# RCPCell.net
KiCad netlist of a schematic drawn in EAGLE
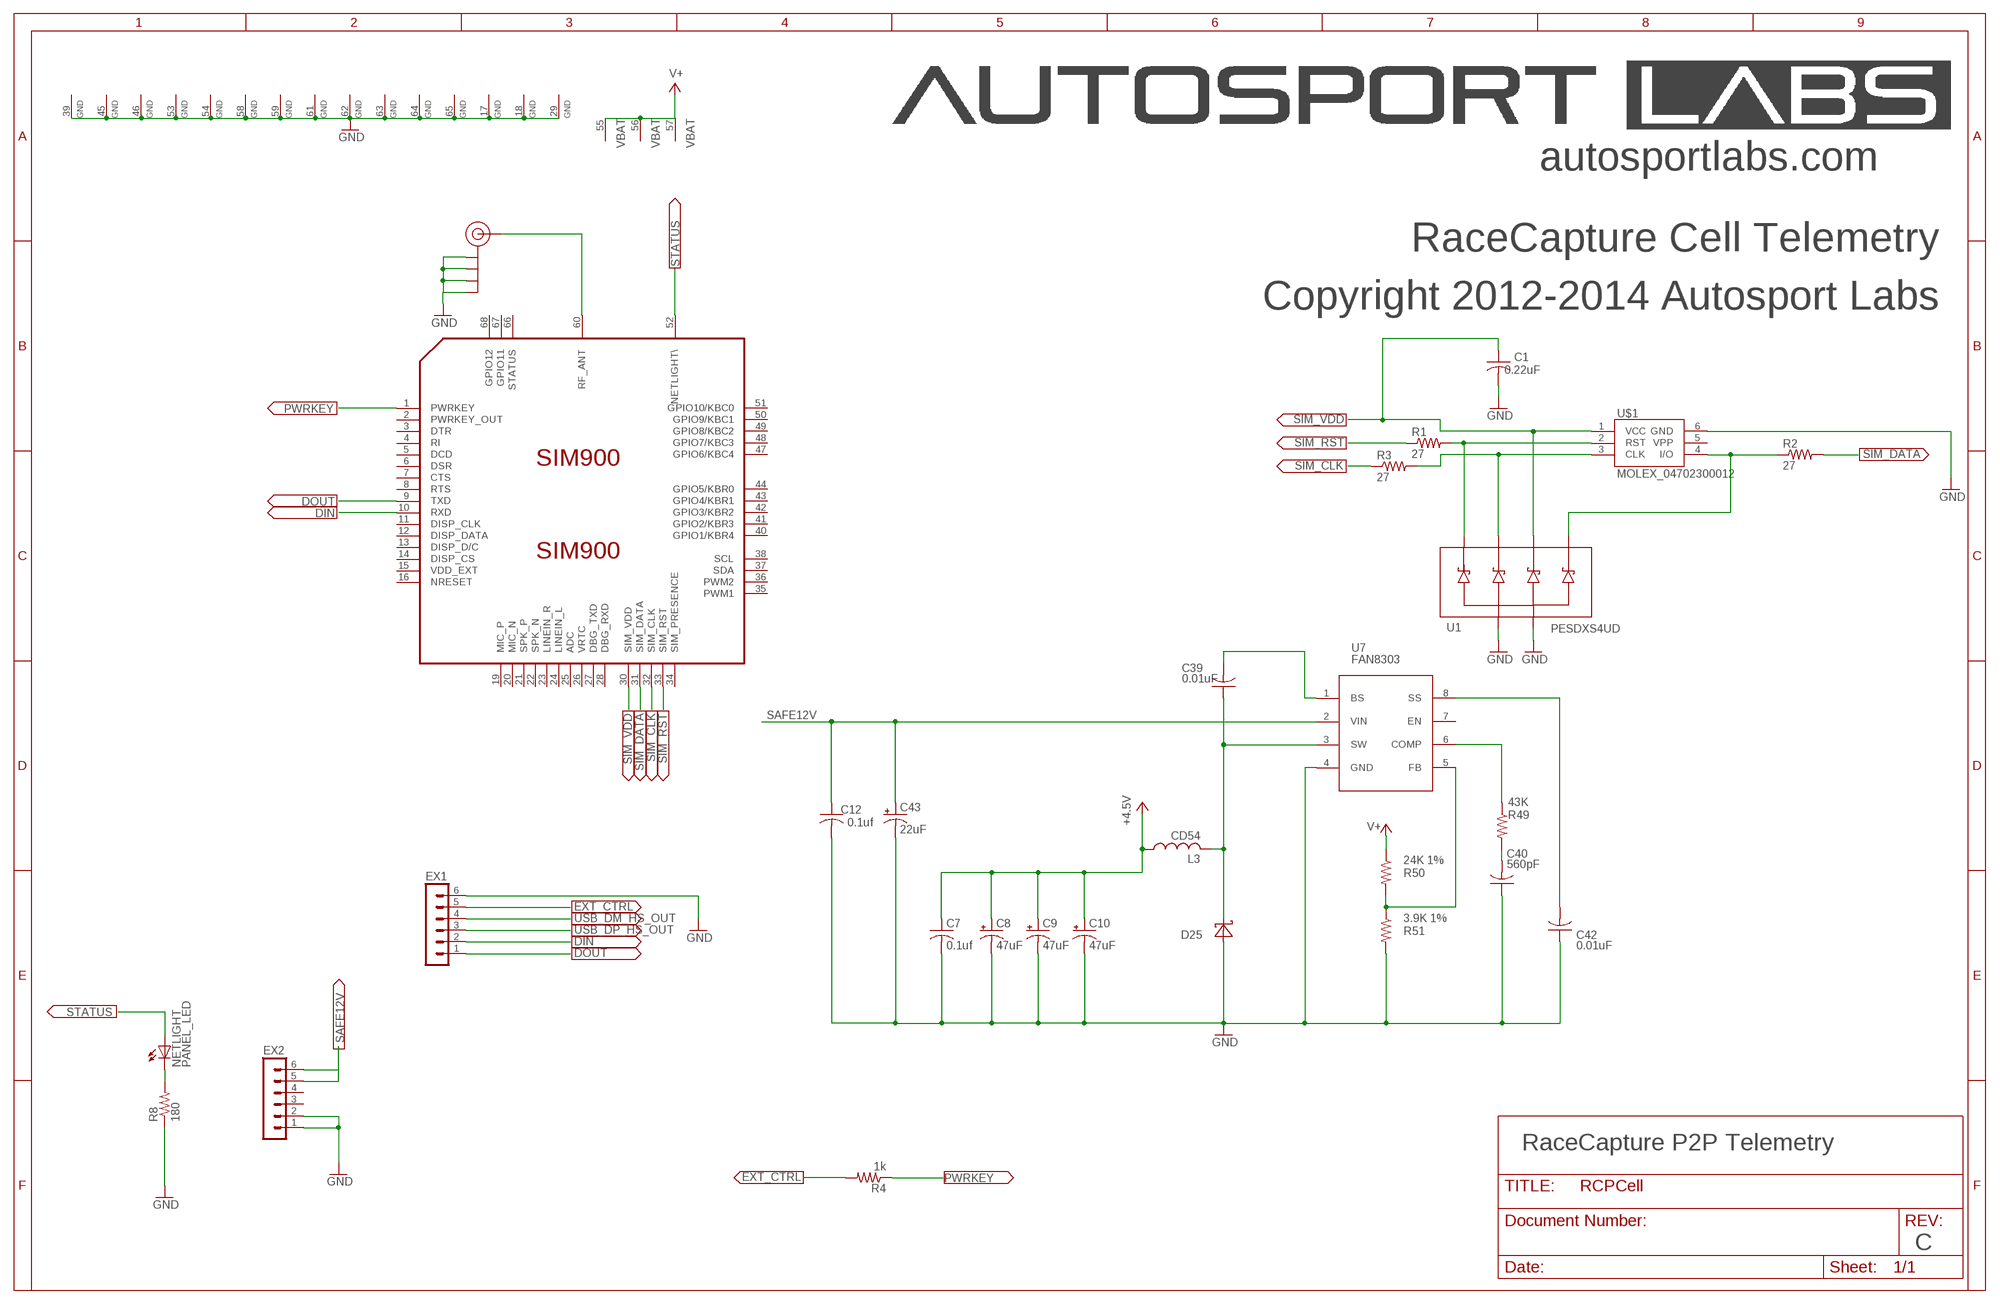
[diagram p0: schematic, sheet 1]

(export (version "E")
  (design (tool "Eeschema 10.0.6"))
  (components
    (comp (ref "C1")
      (value "0.22uF")
      (footprint "eagle-import:C0603")
      (libsource (lib "eagle-import") (part "C-USC0603"))
    )
    (comp (ref "C7")
      (value "0.1uf")
      (footprint "eagle-import:C0603")
      (libsource (lib "eagle-import") (part "C-USC0603"))
    )
    (comp (ref "C8")
      (value "47uF")
      (footprint "eagle-import:SMC_D")
      (libsource (lib "eagle-import") (part "CPOL-USSMCD"))
    )
    (comp (ref "C9")
      (value "47uF")
      (footprint "eagle-import:SMC_D")
      (libsource (lib "eagle-import") (part "CPOL-USSMCD"))
    )
    (comp (ref "C10")
      (value "47uF")
      (footprint "eagle-import:SMC_D")
      (libsource (lib "eagle-import") (part "CPOL-USSMCD"))
    )
    (comp (ref "C12")
      (value "0.1uf")
      (footprint "eagle-import:C0603")
      (libsource (lib "eagle-import") (part "C-USC0603"))
    )
    (comp (ref "C39")
      (value "0.01uF")
      (footprint "eagle-import:C0603")
      (libsource (lib "eagle-import") (part "C-USC0603"))
    )
    (comp (ref "C40")
      (value "560pF")
      (footprint "eagle-import:C0603")
      (libsource (lib "eagle-import") (part "C-USC0603"))
    )
    (comp (ref "C42")
      (value "0.01uF")
      (footprint "eagle-import:C0603")
      (libsource (lib "eagle-import") (part "C-USC0603"))
    )
    (comp (ref "C43")
      (value "22uF")
      (footprint "eagle-import:153CLV-0605")
      (libsource (lib "eagle-import") (part "CPOL-US153CLV-0605"))
    )
    (comp (ref "D25")
      (value "SCHOTTKY")
      (footprint "eagle-import:SMA")
      (libsource (lib "eagle-import") (part "SCHOTTKY"))
    )
    (comp (ref "EX1")
      (value "MA06-1")
      (footprint "eagle-import:MA06-1")
      (libsource (lib "eagle-import") (part "MA06-1"))
    )
    (comp (ref "EX2")
      (value "MA06-1")
      (footprint "eagle-import:MA06-1")
      (libsource (lib "eagle-import") (part "MA06-1"))
    )
    (comp (ref "J$1")
      (value "SMA_EDGE")
      (footprint "eagle-import:SMA-EDGE")
      (libsource (lib "eagle-import") (part "SMA_EDGE"))
    )
    (comp (ref "L3")
      (value "CD54")
      (footprint "eagle-import:CD54")
      (libsource (lib "eagle-import") (part "CD54"))
    )
    (comp (ref "NETLIGHT")
      (value "PANEL_LED")
      (footprint "eagle-import:RIGHTANGLE_CML_5323F5")
      (libsource (lib "eagle-import") (part "PANEL_LED"))
    )
    (comp (ref "R1")
      (value "27")
      (footprint "eagle-import:0603")
      (libsource (lib "eagle-import") (part "RESISTOR0603"))
    )
    (comp (ref "R2")
      (value "27")
      (footprint "eagle-import:0603")
      (libsource (lib "eagle-import") (part "RESISTOR0603"))
    )
    (comp (ref "R3")
      (value "27")
      (footprint "eagle-import:0603")
      (libsource (lib "eagle-import") (part "RESISTOR0603"))
    )
    (comp (ref "R4")
      (value "1k")
      (footprint "eagle-import:0603")
      (libsource (lib "eagle-import") (part "RESISTOR0603"))
    )
    (comp (ref "R8")
      (value "180")
      (footprint "eagle-import:0603")
      (libsource (lib "eagle-import") (part "RESISTOR0603"))
    )
    (comp (ref "R49")
      (value "43K")
      (footprint "eagle-import:R0603")
      (libsource (lib "eagle-import") (part "R-US_R0603"))
    )
    (comp (ref "R50")
      (value "24K 1%")
      (footprint "eagle-import:R0603")
      (libsource (lib "eagle-import") (part "R-US_R0603"))
    )
    (comp (ref "R51")
      (value "3.9K 1%")
      (footprint "eagle-import:R0603")
      (libsource (lib "eagle-import") (part "R-US_R0603"))
    )
    (comp (ref "SIM900")
      (value "SIM900")
      (footprint "eagle-import:SIM900")
      (libsource (lib "eagle-import") (part "SIM900"))
    )
    (comp (ref "U$1")
      (value "MOLEX_04702300012")
      (footprint "eagle-import:MOLEX_91228-3001")
      (libsource (lib "eagle-import") (part "MOLEX_04702300012"))
    )
    (comp (ref "U1")
      (value "PESDXS4UD")
      (footprint "eagle-import:SC-74")
      (libsource (lib "eagle-import") (part "PESDXS4UD"))
    )
    (comp (ref "U7")
      (value "FAN8303")
      (footprint "eagle-import:SO-8")
      (libsource (lib "eagle-import") (part "FAN8303"))
    )
  )
  (nets
    (net (code "1") (name "+4.5V") (class "Default")
      (node (ref "C10") (pin "+") (pinfunction "+_+") (pintype "passive"))
      (node (ref "C7") (pin "1") (pinfunction "1_1") (pintype "passive"))
      (node (ref "C8") (pin "+") (pinfunction "+_+") (pintype "passive"))
      (node (ref "C9") (pin "+") (pinfunction "+_+") (pintype "passive"))
      (node (ref "L3") (pin "P$1") (pinfunction "1_P$1") (pintype "passive"))
      (node (ref "R50") (pin "1") (pinfunction "1_1") (pintype "passive"))
      (node (ref "SIM900") (pin "55") (pinfunction "VBAT_55") (pintype "power_in"))
      (node (ref "SIM900") (pin "56") (pinfunction "VBAT_56") (pintype "power_in"))
      (node (ref "SIM900") (pin "57") (pinfunction "VBAT_57") (pintype "power_in"))
    )
    (net (code "2") (name "/DIN") (class "Default")
      (node (ref "EX1") (pin "2") (pinfunction "2_2") (pintype "passive"))
      (node (ref "SIM900") (pin "10") (pinfunction "RXD_10") (pintype "bidirectional"))
    )
    (net (code "3") (name "/DOUT") (class "Default")
      (node (ref "EX1") (pin "1") (pinfunction "1_1") (pintype "passive"))
      (node (ref "SIM900") (pin "9") (pinfunction "TXD_9") (pintype "bidirectional"))
    )
    (net (code "4") (name "/EXT_CTRL") (class "Default")
      (node (ref "EX1") (pin "5") (pinfunction "5_5") (pintype "passive"))
      (node (ref "R4") (pin "2") (pinfunction "2_2") (pintype "passive"))
    )
    (net (code "5") (name "/PWRKEY") (class "Default")
      (node (ref "R4") (pin "1") (pinfunction "1_1") (pintype "passive"))
      (node (ref "SIM900") (pin "1") (pinfunction "PWRKEY_1") (pintype "bidirectional"))
    )
    (net (code "6") (name "/SAFE12V") (class "Default")
      (node (ref "C12") (pin "1") (pinfunction "1_1") (pintype "passive"))
      (node (ref "C43") (pin "+") (pinfunction "+_+") (pintype "passive"))
      (node (ref "EX2") (pin "5") (pinfunction "5_5") (pintype "passive"))
      (node (ref "EX2") (pin "6") (pinfunction "6_6") (pintype "passive"))
      (node (ref "U7") (pin "2") (pinfunction "VIN_2") (pintype "bidirectional"))
    )
    (net (code "7") (name "/SIM_CLK") (class "Default")
      (node (ref "R3") (pin "1") (pinfunction "1_1") (pintype "passive"))
      (node (ref "SIM900") (pin "32") (pinfunction "SIM_CLK_32") (pintype "bidirectional"))
    )
    (net (code "8") (name "/SIM_DATA") (class "Default")
      (node (ref "R2") (pin "2") (pinfunction "2_2") (pintype "passive"))
      (node (ref "SIM900") (pin "31") (pinfunction "SIM_DATA_31") (pintype "bidirectional"))
    )
    (net (code "9") (name "/SIM_RST") (class "Default")
      (node (ref "R1") (pin "1") (pinfunction "1_1") (pintype "passive"))
      (node (ref "SIM900") (pin "33") (pinfunction "SIM_RST_33") (pintype "bidirectional"))
    )
    (net (code "10") (name "/SIM_VDD") (class "Default")
      (node (ref "C1") (pin "1") (pinfunction "1_1") (pintype "passive"))
      (node (ref "SIM900") (pin "30") (pinfunction "SIM_VDD_30") (pintype "bidirectional"))
      (node (ref "U$1") (pin "1") (pinfunction "VCC_1") (pintype "bidirectional"))
      (node (ref "U1") (pin "4") (pinfunction "4_4") (pintype "passive"))
    )
    (net (code "11") (name "/STATUS") (class "Default")
      (node (ref "NETLIGHT") (pin "A") (pinfunction "A_A") (pintype "passive"))
      (node (ref "SIM900") (pin "52") (pinfunction "NETLIGHT\\_52") (pintype "bidirectional"))
    )
    (net (code "12") (name "/USB_DM_HS_OUT") (class "Default")
      (node (ref "EX1") (pin "4") (pinfunction "4_4") (pintype "passive"))
    )
    (net (code "13") (name "/USB_DP_HS_OUT") (class "Default")
      (node (ref "EX1") (pin "3") (pinfunction "3_3") (pintype "passive"))
    )
    (net (code "14") (name "GND") (class "Default")
      (node (ref "C1") (pin "2") (pinfunction "2_2") (pintype "passive"))
      (node (ref "C10") (pin "-") (pinfunction "-_-") (pintype "passive"))
      (node (ref "C12") (pin "2") (pinfunction "2_2") (pintype "passive"))
      (node (ref "C40") (pin "1") (pinfunction "1_1") (pintype "passive"))
      (node (ref "C42") (pin "1") (pinfunction "1_1") (pintype "passive"))
      (node (ref "C43") (pin "-") (pinfunction "-_-") (pintype "passive"))
      (node (ref "C7") (pin "2") (pinfunction "2_2") (pintype "passive"))
      (node (ref "C8") (pin "-") (pinfunction "-_-") (pintype "passive"))
      (node (ref "C9") (pin "-") (pinfunction "-_-") (pintype "passive"))
      (node (ref "D25") (pin "A") (pinfunction "A_A") (pintype "passive"))
      (node (ref "EX1") (pin "6") (pinfunction "6_6") (pintype "passive"))
      (node (ref "EX2") (pin "1") (pinfunction "1_1") (pintype "passive"))
      (node (ref "EX2") (pin "2") (pinfunction "2_2") (pintype "passive"))
      (node (ref "J$1") (pin "GND@0") (pinfunction "GND_GND@0") (pintype "bidirectional"))
      (node (ref "J$1") (pin "GND@1") (pinfunction "GND_GND@1") (pintype "bidirectional"))
      (node (ref "J$1") (pin "GND@2") (pinfunction "GND_GND@2") (pintype "bidirectional"))
      (node (ref "J$1") (pin "GND@3") (pinfunction "GND_GND@3") (pintype "bidirectional"))
      (node (ref "R51") (pin "2") (pinfunction "2_2") (pintype "passive"))
      (node (ref "R8") (pin "1") (pinfunction "1_1") (pintype "passive"))
      (node (ref "SIM900") (pin "17") (pinfunction "GND_17") (pintype "power_in"))
      (node (ref "SIM900") (pin "18") (pinfunction "GND_18") (pintype "power_in"))
      (node (ref "SIM900") (pin "29") (pinfunction "GND_29") (pintype "power_in"))
      (node (ref "SIM900") (pin "39") (pinfunction "GND_39") (pintype "power_in"))
      (node (ref "SIM900") (pin "45") (pinfunction "GND_45") (pintype "power_in"))
      (node (ref "SIM900") (pin "46") (pinfunction "GND_46") (pintype "power_in"))
      (node (ref "SIM900") (pin "53") (pinfunction "GND_53") (pintype "power_in"))
      (node (ref "SIM900") (pin "54") (pinfunction "GND_54") (pintype "power_in"))
      (node (ref "SIM900") (pin "58") (pinfunction "GND_58") (pintype "power_in"))
      (node (ref "SIM900") (pin "59") (pinfunction "GND_59") (pintype "power_in"))
      (node (ref "SIM900") (pin "61") (pinfunction "GND_61") (pintype "power_in"))
      (node (ref "SIM900") (pin "62") (pinfunction "GND_62") (pintype "power_in"))
      (node (ref "SIM900") (pin "63") (pinfunction "GND_63") (pintype "power_in"))
      (node (ref "SIM900") (pin "64") (pinfunction "GND_64") (pintype "power_in"))
      (node (ref "SIM900") (pin "65") (pinfunction "GND_65") (pintype "power_in"))
      (node (ref "U$1") (pin "6") (pinfunction "GND_6") (pintype "bidirectional"))
      (node (ref "U1") (pin "2") (pinfunction "2_2") (pintype "passive"))
      (node (ref "U1") (pin "5") (pinfunction "5_5") (pintype "passive"))
      (node (ref "U7") (pin "4") (pinfunction "GND_4") (pintype "bidirectional"))
    )
    (net (code "15") (name "Net-(C40-Pad2)") (class "Default")
      (node (ref "C40") (pin "2") (pinfunction "2_2") (pintype "passive"))
      (node (ref "R49") (pin "2") (pinfunction "2_2") (pintype "passive"))
    )
    (net (code "16") (name "Net-(J$1-SIGNAL)") (class "Default")
      (node (ref "J$1") (pin "SIG") (pinfunction "SIGNAL_SIG") (pintype "bidirectional"))
      (node (ref "SIM900") (pin "60") (pinfunction "RF_ANT_60") (pintype "bidirectional"))
    )
    (net (code "17") (name "Net-(L3-2)") (class "Default")
      (node (ref "C39") (pin "1") (pinfunction "1_1") (pintype "passive"))
      (node (ref "D25") (pin "C") (pinfunction "C_C") (pintype "passive"))
      (node (ref "L3") (pin "P$2") (pinfunction "2_P$2") (pintype "passive"))
      (node (ref "U7") (pin "3") (pinfunction "SW_3") (pintype "bidirectional"))
    )
    (net (code "18") (name "Net-(NETLIGHT-PadC)") (class "Default")
      (node (ref "NETLIGHT") (pin "C") (pinfunction "C_C") (pintype "passive"))
      (node (ref "R8") (pin "2") (pinfunction "2_2") (pintype "passive"))
    )
    (net (code "19") (name "Net-(U$1-CLK)") (class "Default")
      (node (ref "R3") (pin "2") (pinfunction "2_2") (pintype "passive"))
      (node (ref "U$1") (pin "3") (pinfunction "CLK_3") (pintype "bidirectional"))
      (node (ref "U1") (pin "3") (pinfunction "3_3") (pintype "passive"))
    )
    (net (code "20") (name "Net-(U$1-I{slash}O)") (class "Default")
      (node (ref "R2") (pin "1") (pinfunction "1_1") (pintype "passive"))
      (node (ref "U$1") (pin "4") (pinfunction "I/O_4") (pintype "bidirectional"))
      (node (ref "U1") (pin "6") (pinfunction "6_6") (pintype "passive"))
    )
    (net (code "21") (name "Net-(U$1-RST)") (class "Default")
      (node (ref "R1") (pin "2") (pinfunction "2_2") (pintype "passive"))
      (node (ref "U$1") (pin "2") (pinfunction "RST_2") (pintype "bidirectional"))
      (node (ref "U1") (pin "1") (pinfunction "1_1") (pintype "passive"))
    )
    (net (code "22") (name "Net-(U7-BS)") (class "Default")
      (node (ref "C39") (pin "2") (pinfunction "2_2") (pintype "passive"))
      (node (ref "U7") (pin "1") (pinfunction "BS_1") (pintype "bidirectional"))
    )
    (net (code "23") (name "Net-(U7-COMP)") (class "Default")
      (node (ref "R49") (pin "1") (pinfunction "1_1") (pintype "passive"))
      (node (ref "U7") (pin "6") (pinfunction "COMP_6") (pintype "bidirectional"))
    )
    (net (code "24") (name "Net-(U7-FB)") (class "Default")
      (node (ref "R50") (pin "2") (pinfunction "2_2") (pintype "passive"))
      (node (ref "R51") (pin "1") (pinfunction "1_1") (pintype "passive"))
      (node (ref "U7") (pin "5") (pinfunction "FB_5") (pintype "bidirectional"))
    )
    (net (code "25") (name "Net-(U7-SS)") (class "Default")
      (node (ref "C42") (pin "2") (pinfunction "2_2") (pintype "passive"))
      (node (ref "U7") (pin "8") (pinfunction "SS_8") (pintype "bidirectional"))
    )
    (net (code "26") (name "unconnected-(EX2-Pad3)") (class "Default")
      (node (ref "EX2") (pin "3") (pinfunction "3_3") (pintype "passive"))
    )
    (net (code "27") (name "unconnected-(EX2-Pad4)") (class "Default")
      (node (ref "EX2") (pin "4") (pinfunction "4_4") (pintype "passive"))
    )
    (net (code "28") (name "unconnected-(SIM900A-ADC-Pad25)") (class "Default")
      (node (ref "SIM900") (pin "25") (pinfunction "ADC_25") (pintype "bidirectional"))
    )
    (net (code "29") (name "unconnected-(SIM900A-CTS-Pad7)") (class "Default")
      (node (ref "SIM900") (pin "7") (pinfunction "CTS_7") (pintype "bidirectional"))
    )
    (net (code "30") (name "unconnected-(SIM900A-DBG_RXD-Pad28)") (class "Default")
      (node (ref "SIM900") (pin "28") (pinfunction "DBG_RXD_28") (pintype "bidirectional"))
    )
    (net (code "31") (name "unconnected-(SIM900A-DBG_TXD-Pad27)") (class "Default")
      (node (ref "SIM900") (pin "27") (pinfunction "DBG_TXD_27") (pintype "bidirectional"))
    )
    (net (code "32") (name "unconnected-(SIM900A-DCD-Pad5)") (class "Default")
      (node (ref "SIM900") (pin "5") (pinfunction "DCD_5") (pintype "bidirectional"))
    )
    (net (code "33") (name "unconnected-(SIM900A-DISP_CLK-Pad11)") (class "Default")
      (node (ref "SIM900") (pin "11") (pinfunction "DISP_CLK_11") (pintype "bidirectional"))
    )
    (net (code "34") (name "unconnected-(SIM900A-DISP_CS-Pad14)") (class "Default")
      (node (ref "SIM900") (pin "14") (pinfunction "DISP_CS_14") (pintype "bidirectional"))
    )
    (net (code "35") (name "unconnected-(SIM900A-DISP_DATA-Pad12)") (class "Default")
      (node (ref "SIM900") (pin "12") (pinfunction "DISP_DATA_12") (pintype "bidirectional"))
    )
    (net (code "36") (name "unconnected-(SIM900A-DISP_D{slash}C-Pad13)") (class "Default")
      (node (ref "SIM900") (pin "13") (pinfunction "DISP_D/C_13") (pintype "bidirectional"))
    )
    (net (code "37") (name "unconnected-(SIM900A-DSR-Pad6)") (class "Default")
      (node (ref "SIM900") (pin "6") (pinfunction "DSR_6") (pintype "bidirectional"))
    )
    (net (code "38") (name "unconnected-(SIM900A-DTR-Pad3)") (class "Default")
      (node (ref "SIM900") (pin "3") (pinfunction "DTR_3") (pintype "bidirectional"))
    )
    (net (code "39") (name "unconnected-(SIM900A-GPIO1{slash}KBR4-Pad40)") (class "Default")
      (node (ref "SIM900") (pin "40") (pinfunction "GPIO1/KBR4_40") (pintype "bidirectional"))
    )
    (net (code "40") (name "unconnected-(SIM900A-GPIO2{slash}KBR3-Pad41)") (class "Default")
      (node (ref "SIM900") (pin "41") (pinfunction "GPIO2/KBR3_41") (pintype "bidirectional"))
    )
    (net (code "41") (name "unconnected-(SIM900A-GPIO3{slash}KBR2-Pad42)") (class "Default")
      (node (ref "SIM900") (pin "42") (pinfunction "GPIO3/KBR2_42") (pintype "bidirectional"))
    )
    (net (code "42") (name "unconnected-(SIM900A-GPIO4{slash}KBR1-Pad43)") (class "Default")
      (node (ref "SIM900") (pin "43") (pinfunction "GPIO4/KBR1_43") (pintype "bidirectional"))
    )
    (net (code "43") (name "unconnected-(SIM900A-GPIO5{slash}KBR0-Pad44)") (class "Default")
      (node (ref "SIM900") (pin "44") (pinfunction "GPIO5/KBR0_44") (pintype "bidirectional"))
    )
    (net (code "44") (name "unconnected-(SIM900A-GPIO6{slash}KBC4-Pad47)") (class "Default")
      (node (ref "SIM900") (pin "47") (pinfunction "GPIO6/KBC4_47") (pintype "bidirectional"))
    )
    (net (code "45") (name "unconnected-(SIM900A-GPIO7{slash}KBC3-Pad48)") (class "Default")
      (node (ref "SIM900") (pin "48") (pinfunction "GPIO7/KBC3_48") (pintype "bidirectional"))
    )
    (net (code "46") (name "unconnected-(SIM900A-GPIO8{slash}KBC2-Pad49)") (class "Default")
      (node (ref "SIM900") (pin "49") (pinfunction "GPIO8/KBC2_49") (pintype "bidirectional"))
    )
    (net (code "47") (name "unconnected-(SIM900A-GPIO9{slash}KBC1-Pad50)") (class "Default")
      (node (ref "SIM900") (pin "50") (pinfunction "GPIO9/KBC1_50") (pintype "bidirectional"))
    )
    (net (code "48") (name "unconnected-(SIM900A-GPIO10{slash}KBC0-Pad51)") (class "Default")
      (node (ref "SIM900") (pin "51") (pinfunction "GPIO10/KBC0_51") (pintype "bidirectional"))
    )
    (net (code "49") (name "unconnected-(SIM900A-GPIO11-Pad67)") (class "Default")
      (node (ref "SIM900") (pin "67") (pinfunction "GPIO11_67") (pintype "bidirectional"))
    )
    (net (code "50") (name "unconnected-(SIM900A-GPIO12-Pad68)") (class "Default")
      (node (ref "SIM900") (pin "68") (pinfunction "GPIO12_68") (pintype "bidirectional"))
    )
    (net (code "51") (name "unconnected-(SIM900A-LINEIN_L-Pad24)") (class "Default")
      (node (ref "SIM900") (pin "24") (pinfunction "LINEIN_L_24") (pintype "bidirectional"))
    )
    (net (code "52") (name "unconnected-(SIM900A-LINEIN_R-Pad23)") (class "Default")
      (node (ref "SIM900") (pin "23") (pinfunction "LINEIN_R_23") (pintype "bidirectional"))
    )
    (net (code "53") (name "unconnected-(SIM900A-MIC_N-Pad20)") (class "Default")
      (node (ref "SIM900") (pin "20") (pinfunction "MIC_N_20") (pintype "bidirectional"))
    )
    (net (code "54") (name "unconnected-(SIM900A-MIC_P-Pad19)") (class "Default")
      (node (ref "SIM900") (pin "19") (pinfunction "MIC_P_19") (pintype "bidirectional"))
    )
    (net (code "55") (name "unconnected-(SIM900A-NRESET-Pad16)") (class "Default")
      (node (ref "SIM900") (pin "16") (pinfunction "NRESET_16") (pintype "bidirectional"))
    )
    (net (code "56") (name "unconnected-(SIM900A-PWM1-Pad35)") (class "Default")
      (node (ref "SIM900") (pin "35") (pinfunction "PWM1_35") (pintype "bidirectional"))
    )
    (net (code "57") (name "unconnected-(SIM900A-PWM2-Pad36)") (class "Default")
      (node (ref "SIM900") (pin "36") (pinfunction "PWM2_36") (pintype "bidirectional"))
    )
    (net (code "58") (name "unconnected-(SIM900A-PWRKEY_OUT-Pad2)") (class "Default")
      (node (ref "SIM900") (pin "2") (pinfunction "PWRKEY_OUT_2") (pintype "bidirectional"))
    )
    (net (code "59") (name "unconnected-(SIM900A-RI-Pad4)") (class "Default")
      (node (ref "SIM900") (pin "4") (pinfunction "RI_4") (pintype "bidirectional"))
    )
    (net (code "60") (name "unconnected-(SIM900A-RTS-Pad8)") (class "Default")
      (node (ref "SIM900") (pin "8") (pinfunction "RTS_8") (pintype "bidirectional"))
    )
    (net (code "61") (name "unconnected-(SIM900A-SCL-Pad38)") (class "Default")
      (node (ref "SIM900") (pin "38") (pinfunction "SCL_38") (pintype "bidirectional"))
    )
    (net (code "62") (name "unconnected-(SIM900A-SDA-Pad37)") (class "Default")
      (node (ref "SIM900") (pin "37") (pinfunction "SDA_37") (pintype "bidirectional"))
    )
    (net (code "63") (name "unconnected-(SIM900A-SIM_PRESENCE-Pad34)") (class "Default")
      (node (ref "SIM900") (pin "34") (pinfunction "SIM_PRESENCE_34") (pintype "bidirectional"))
    )
    (net (code "64") (name "unconnected-(SIM900A-SPK_N-Pad22)") (class "Default")
      (node (ref "SIM900") (pin "22") (pinfunction "SPK_N_22") (pintype "bidirectional"))
    )
    (net (code "65") (name "unconnected-(SIM900A-SPK_P-Pad21)") (class "Default")
      (node (ref "SIM900") (pin "21") (pinfunction "SPK_P_21") (pintype "bidirectional"))
    )
    (net (code "66") (name "unconnected-(SIM900A-STATUS-Pad66)") (class "Default")
      (node (ref "SIM900") (pin "66") (pinfunction "STATUS_66") (pintype "bidirectional"))
    )
    (net (code "67") (name "unconnected-(SIM900A-VDD_EXT-Pad15)") (class "Default")
      (node (ref "SIM900") (pin "15") (pinfunction "VDD_EXT_15") (pintype "bidirectional"))
    )
    (net (code "68") (name "unconnected-(SIM900A-VRTC-Pad26)") (class "Default")
      (node (ref "SIM900") (pin "26") (pinfunction "VRTC_26") (pintype "bidirectional"))
    )
    (net (code "69") (name "unconnected-(U$1-VPP-Pad5)") (class "Default")
      (node (ref "U$1") (pin "5") (pinfunction "VPP_5") (pintype "bidirectional"))
    )
    (net (code "70") (name "unconnected-(U7-EN-Pad7)") (class "Default")
      (node (ref "U7") (pin "7") (pinfunction "EN_7") (pintype "bidirectional"))
    )
  )
)
